# 3V3_NCP1117DT33G.net
KiCad netlist of a schematic drawn in Altium Designer
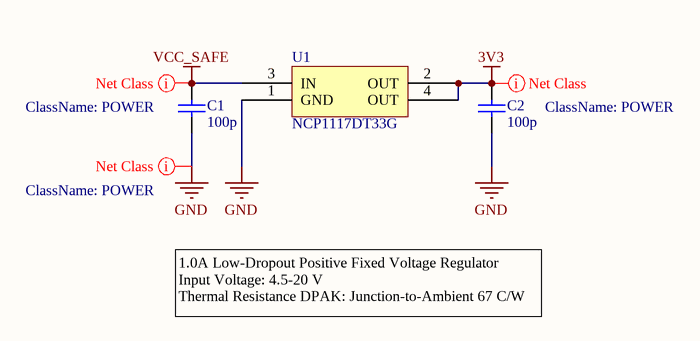
[diagram p0: 3V3 NCP1117DT33G.SchDoc]

(export (version "E")
  (design (tool "Eeschema 10.0.6"))
  (components
    (comp (ref "C1")
      (value "100p")
      (footprint "agh_racing_2018:CAP_0603_IPC_MD")
      (description "Capacitor")
      (fields (field (name "Comment") "Cap"))
      (libsource (lib "agh_racing_2018") (part "Cap"))
    )
    (comp (ref "C2")
      (value "100p")
      (footprint "agh_racing_2018:CAP_0603_IPC_MD")
      (description "Capacitor")
      (fields (field (name "Comment") "Cap"))
      (libsource (lib "agh_racing_2018") (part "Cap"))
    )
    (comp (ref "U1")
      (value "NCP1117DT33G")
      (footprint "agh_racing_2018:DPAK_IPC_MD")
      (libsource (lib "agh_racing_2018") (part "NCP1117DT33G"))
    )
  )
  (nets
    (net (code "1") (name "3V3") (class "Default")
      (node (ref "C2") (pin "2") (pinfunction "2_2") (pintype "passive"))
      (node (ref "U1") (pin "2") (pinfunction "OUT_2") (pintype "power_in"))
      (node (ref "U1") (pin "4") (pinfunction "OUT_4") (pintype "power_in"))
    )
    (net (code "2") (name "GND") (class "Default")
      (node (ref "C1") (pin "1") (pinfunction "1_1") (pintype "passive"))
      (node (ref "C2") (pin "1") (pinfunction "1_1") (pintype "passive"))
      (node (ref "U1") (pin "1") (pinfunction "GND_1") (pintype "power_in"))
    )
    (net (code "3") (name "VCC_SAFE") (class "Default")
      (node (ref "C1") (pin "2") (pinfunction "2_2") (pintype "passive"))
      (node (ref "U1") (pin "3") (pinfunction "IN_3") (pintype "power_in"))
    )
  )
)
